# GPS.net
KiCad netlist of a schematic drawn in Altium Designer
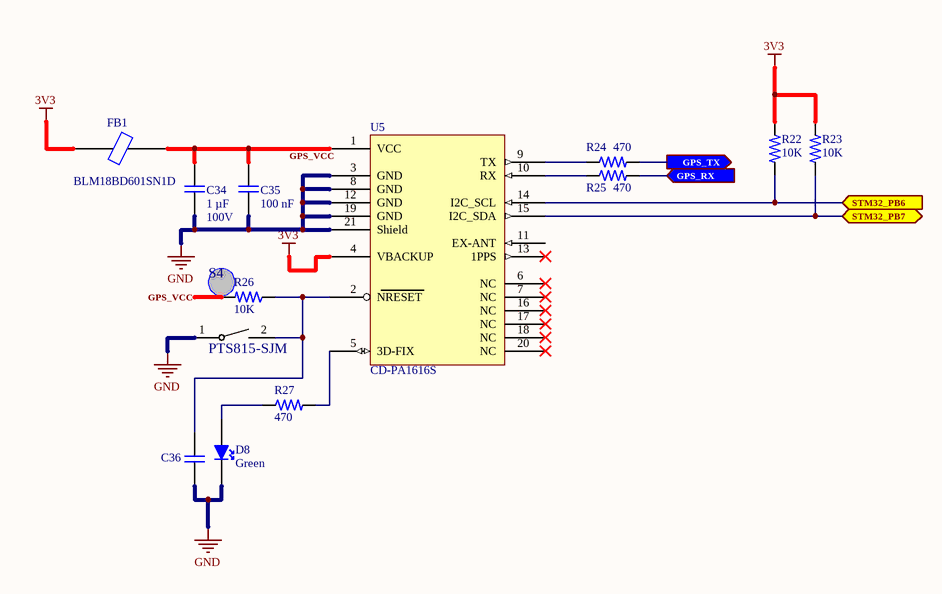
[diagram p0: GPS.SchDoc]

(export (version "E")
  (design (tool "Eeschema 10.0.6"))
  (components
    (comp (ref "C34")
      (value "1 µF")
      (footprint "MergenElektronik_Capacitors_Ceramics_SMDs_1206_M_NS")
      (description "Mergen Elektronik - Capacitors - Ceramics - SMDs - 1206 - 1 µF - 100V")
      (fields
        (field (name "MANUFACTURER") "Samsung Electro-Mechanics")
        (field (name "TOLERANCE") "±10%")
        (field (name "VOLTAGE RATING") "100V")
      )
      (libsource (lib "MergenElektronik_Capacitors_Ceramics_SMDs") (part "MergenElektronik_Capacitors_Ceramic_SMDs_1µF_100V"))
    )
    (comp (ref "C35")
      (value "100 nF")
      (footprint "MergenElektronik_Capacitors_Ceramics_SMDs_0603_M_NS")
      (description "Mergen Elektronik - Capacitors - Ceramics - SMDs - 0603 - 100 nF - 100V")
      (fields (field (name "MANUFACTURER") "Samsung Electro-Mechanics") (field (name "TOLERANCE") "±10%"))
      (libsource (lib "MergenElektronik_Capacitors_Ceramics_SMDs") (part "MergenElektronik_Capacitors_Ceramic_SMDs_100nF_100V"))
    )
    (comp (ref "C36")
      (value "100 nF")
      (footprint "MergenElektronik_Capacitors_Ceramics_SMDs_0603_M_NS")
      (description "Mergen Elektronik - Capacitors - Ceramics - SMDs - 0603 - 100 nF - 100V")
      (fields (field (name "MANUFACTURER") "Samsung Electro-Mechanics") (field (name "TOLERANCE") "±10%"))
      (libsource (lib "MergenElektronik_Capacitors_Ceramics_SMDs") (part "MergenElektronik_Capacitors_Ceramic_SMDs_100nF_100V"))
    )
    (comp (ref "D8")
      (value "Green")
      (footprint "MergenElektronik_Leds_SMDs_0603_M_NS")
      (description "Mergen Elektronik - Leds - SMDs - Green - 0603")
      (fields (field (name "MANUFACTURER") "Würth Elektronik"))
      (libsource (lib "MergenElektronik_Leds_SMDs") (part "MergenElektronik_LEDs_SMDs_Green_0603"))
    )
    (comp (ref "FB1")
      (value "BLM18BD601SN1D")
      (footprint "MergenElektronik_Filters_FerriteBeads_0603_M_NS")
      (description "Mergen Elektronik - Filters - Ferrite Beads - BLM18BD601SN1D")
      (fields (field (name "MANUFACTURER") "Murata Electronics"))
      (libsource (lib "MergenElektronik_Filters_FerriteBeads") (part "MergenElektronik_Filters_FerriteBeads_BLM18BD601SN1D"))
    )
    (comp (ref "R22")
      (value "10K")
      (footprint "MergenElektronik_Resistors_ChipResistors_0603_M_NS")
      (description "Mergen Elektronik - Resistors - Chip Resistors - 0603 - 10K")
      (fields (field (name "MANUFACTURER") "Stackpole Electronics Inc") (field (name "POWER") "1/10W"))
      (libsource (lib "MergenElektronik_Resistors_ChipResistors") (part "MergenElektronik_Resistors_ChipResistors_0603_10K"))
    )
    (comp (ref "R23")
      (value "10K")
      (footprint "MergenElektronik_Resistors_ChipResistors_0603_M_NS")
      (description "Mergen Elektronik - Resistors - Chip Resistors - 0603 - 10K")
      (fields (field (name "MANUFACTURER") "Stackpole Electronics Inc") (field (name "POWER") "1/10W"))
      (libsource (lib "MergenElektronik_Resistors_ChipResistors") (part "MergenElektronik_Resistors_ChipResistors_0603_10K"))
    )
    (comp (ref "R24")
      (value "470")
      (footprint "MergenElektronik_Resistors_ChipResistors_0603_M_NS")
      (description "Mergen Elektronik - Resistors - Chip Resistors - 0603 - 470")
      (fields (field (name "MANUFACTURER") "Stackpole Electronics Inc") (field (name "POWER") "1/10W"))
      (libsource (lib "MergenElektronik_Resistors_ChipResistors") (part "MergenElektronik_Resistors_ChipResistors_0603_470"))
    )
    (comp (ref "R25")
      (value "470")
      (footprint "MergenElektronik_Resistors_ChipResistors_0603_M_NS")
      (description "Mergen Elektronik - Resistors - Chip Resistors - 0603 - 470")
      (fields (field (name "MANUFACTURER") "Stackpole Electronics Inc") (field (name "POWER") "1/10W"))
      (libsource (lib "MergenElektronik_Resistors_ChipResistors") (part "MergenElektronik_Resistors_ChipResistors_0603_470"))
    )
    (comp (ref "R26")
      (value "10K")
      (footprint "MergenElektronik_Resistors_ChipResistors_0603_M_NS")
      (description "Mergen Elektronik - Resistors - Chip Resistors - 0603 - 10K")
      (fields (field (name "MANUFACTURER") "Stackpole Electronics Inc") (field (name "POWER") "1/10W"))
      (libsource (lib "MergenElektronik_Resistors_ChipResistors") (part "MergenElektronik_Resistors_ChipResistors_0603_10K"))
    )
    (comp (ref "R27")
      (value "470")
      (footprint "MergenElektronik_Resistors_ChipResistors_0603_M_NS")
      (description "Mergen Elektronik - Resistors - Chip Resistors - 0603 - 470")
      (fields (field (name "MANUFACTURER") "Stackpole Electronics Inc") (field (name "POWER") "1/10W"))
      (libsource (lib "MergenElektronik_Resistors_ChipResistors") (part "MergenElektronik_Resistors_ChipResistors_0603_470"))
    )
    (comp (ref "S4")
      (value "PTS815-SJM")
      (footprint "MergenElektronik_Switches_TactileSwitches_PTS815")
      (description "Mergen Elektronik - Switches - Tactile  Switches")
      (fields (field (name "MANUFACTURER") "C&K"))
      (libsource (lib "MergenElektronik_Switches_TactileSwitches") (part "MergenElektronik_Switches_TactileSwitches_PTS815-SJM"))
    )
    (comp (ref "U5")
      (value "CD-PA1616S")
      (footprint "MergenElektronik_Modules_GPS_CD-PA1616S")
      (description "Mergen Elektronik -  Modules - GPS - CD-PA1616S")
      (fields
        (field (name "MANUFACTURER") "Adafruit")
        (field (name "TOLERANCE") "< 3 meters")
        (field (name "UPDATE RATE") "1Hz up to 10 Hz")
      )
      (libsource (lib "MergenElektronik_Modules_GPS") (part "MergenElektronik_Modules_GPS"))
    )
  )
  (nets
    (net (code "1") (name "/GPS_RX") (class "Default")
      (node (ref "R25") (pin "2") (pinfunction "2_2") (pintype "passive"))
    )
    (net (code "2") (name "/GPS_TX") (class "Default")
      (node (ref "R24") (pin "2") (pinfunction "2_2") (pintype "passive"))
    )
    (net (code "3") (name "/GPS_VCC") (class "Default")
      (node (ref "C34") (pin "1") (pinfunction "1_1") (pintype "passive"))
      (node (ref "C35") (pin "1") (pinfunction "1_1") (pintype "passive"))
      (node (ref "FB1") (pin "2") (pinfunction "2_2") (pintype "passive"))
      (node (ref "R26") (pin "2") (pinfunction "2_2") (pintype "passive"))
      (node (ref "U5") (pin "1") (pinfunction "VCC_1") (pintype "power_in"))
    )
    (net (code "4") (name "/STM32_PB6") (class "Default")
      (node (ref "R22") (pin "2") (pinfunction "2_2") (pintype "passive"))
      (node (ref "U5") (pin "14") (pinfunction "I2C_SCL_14") (pintype "input"))
    )
    (net (code "5") (name "/STM32_PB7") (class "Default")
      (node (ref "R23") (pin "2") (pinfunction "2_2") (pintype "passive"))
      (node (ref "U5") (pin "15") (pinfunction "I2C_SDA_15") (pintype "output"))
    )
    (net (code "6") (name "3V3") (class "Default")
      (node (ref "FB1") (pin "1") (pinfunction "1_1") (pintype "passive"))
      (node (ref "R22") (pin "1") (pinfunction "1_1") (pintype "passive"))
      (node (ref "R23") (pin "1") (pinfunction "1_1") (pintype "passive"))
      (node (ref "U5") (pin "4") (pinfunction "VBACKUP_4") (pintype "power_in"))
    )
    (net (code "7") (name "GND") (class "Default")
      (node (ref "C34") (pin "2") (pinfunction "2_2") (pintype "passive"))
      (node (ref "C35") (pin "2") (pinfunction "2_2") (pintype "passive"))
      (node (ref "C36") (pin "2") (pinfunction "2_2") (pintype "passive"))
      (node (ref "D8") (pin "2") (pinfunction "KATOT_2") (pintype "passive"))
      (node (ref "S4") (pin "1") (pinfunction "1_1") (pintype "passive"))
      (node (ref "U5") (pin "12") (pinfunction "GND_12") (pintype "power_in"))
      (node (ref "U5") (pin "19") (pinfunction "GND_19") (pintype "power_in"))
      (node (ref "U5") (pin "21") (pinfunction "Shield_21") (pintype "power_in"))
      (node (ref "U5") (pin "3") (pinfunction "GND_3") (pintype "power_in"))
      (node (ref "U5") (pin "8") (pinfunction "GND_8") (pintype "power_in"))
    )
    (net (code "8") (name "Net-(D8-ANOT)") (class "Default")
      (node (ref "D8") (pin "1") (pinfunction "ANOT_1") (pintype "passive"))
      (node (ref "R27") (pin "1") (pinfunction "1_1") (pintype "passive"))
    )
    (net (code "9") (name "Net-(U5-3D-FIX)") (class "Default")
      (node (ref "R27") (pin "2") (pinfunction "2_2") (pintype "passive"))
      (node (ref "U5") (pin "5") (pinfunction "3D-FIX_5") (pintype "bidirectional"))
    )
    (net (code "10") (name "Net-(U5-NRESET)") (class "Default")
      (node (ref "C36") (pin "1") (pinfunction "1_1") (pintype "passive"))
      (node (ref "R26") (pin "1") (pinfunction "1_1") (pintype "passive"))
      (node (ref "S4") (pin "2") (pinfunction "2_2") (pintype "passive"))
      (node (ref "U5") (pin "2") (pinfunction "NRESET_2") (pintype "passive"))
    )
    (net (code "11") (name "Net-(U5-RX)") (class "Default")
      (node (ref "R25") (pin "1") (pinfunction "1_1") (pintype "passive"))
      (node (ref "U5") (pin "10") (pinfunction "RX_10") (pintype "input"))
    )
    (net (code "12") (name "Net-(U5-TX)") (class "Default")
      (node (ref "R24") (pin "1") (pinfunction "1_1") (pintype "passive"))
      (node (ref "U5") (pin "9") (pinfunction "TX_9") (pintype "output"))
    )
    (net (code "13") (name "unconnected-(U5-1PPS-Pad13)") (class "Default")
      (node (ref "U5") (pin "13") (pinfunction "1PPS_13") (pintype "output+no_connect"))
    )
    (net (code "14") (name "unconnected-(U5-EX-ANT-Pad11)") (class "Default")
      (node (ref "U5") (pin "11") (pinfunction "EX-ANT_11") (pintype "input"))
    )
    (net (code "15") (name "unconnected-(U5-NC-Pad6)") (class "Default")
      (node (ref "U5") (pin "6") (pinfunction "NC_6") (pintype "passive+no_connect"))
    )
    (net (code "16") (name "unconnected-(U5-NC-Pad7)") (class "Default")
      (node (ref "U5") (pin "7") (pinfunction "NC_7") (pintype "passive+no_connect"))
    )
    (net (code "17") (name "unconnected-(U5-NC-Pad16)") (class "Default")
      (node (ref "U5") (pin "16") (pinfunction "NC_16") (pintype "passive+no_connect"))
    )
    (net (code "18") (name "unconnected-(U5-NC-Pad17)") (class "Default")
      (node (ref "U5") (pin "17") (pinfunction "NC_17") (pintype "passive+no_connect"))
    )
    (net (code "19") (name "unconnected-(U5-NC-Pad18)") (class "Default")
      (node (ref "U5") (pin "18") (pinfunction "NC_18") (pintype "passive+no_connect"))
    )
    (net (code "20") (name "unconnected-(U5-NC-Pad20)") (class "Default")
      (node (ref "U5") (pin "20") (pinfunction "NC_20") (pintype "passive+no_connect"))
    )
  )
)
